# Bluetooth.net
KiCad netlist of a schematic drawn in Altium Designer
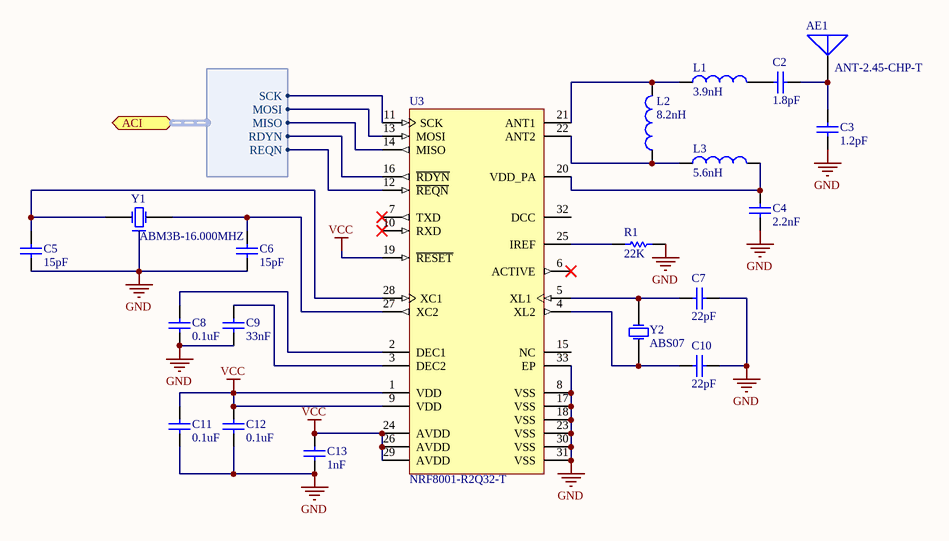
[diagram p0: Bluetooth.SchDoc]

(export (version "E")
  (design (tool "Eeschema 10.0.6"))
  (components
    (comp (ref "AE1")
      (value "ANT-2.45-CHP-T")
      (footprint "ANT-2.45-CHP")
      (fields (field (name "MANUFACTURER") "Taiyo Yuden"))
      (libsource (lib "Components") (part "ANT-2.45-CHP-T"))
    )
    (comp (ref "C2")
      (value "1.8pF")
      (footprint "C0402[1005X55]")
      (description "1.8pF 50V 0.05pF 0402 (1005 Metric)")
      (fields (field (name "PARTNUMBER") "GRM1555C1H1R8WA01D") (field (name "MANUFACTURER") "Murata"))
      (libsource (lib "Capacitors") (part "CAP_1.8pF_50V_0402_0.05pF"))
    )
    (comp (ref "C3")
      (value "1.2pF")
      (footprint "C0402[1005X55]")
      (description "1.2pF 50V 0.05pF 0402 (1005 Metric)")
      (fields (field (name "PARTNUMBER") "GRM1555C1H1R2WA01D") (field (name "MANUFACTURER") "Murata"))
      (libsource (lib "Capacitors") (part "CAP_1.2pF_50V_0402_0.05pF"))
    )
    (comp (ref "C4")
      (value "2.2nF")
      (footprint "C0402[1005X55]")
      (description "2.2nF 50V 10% 0402 (1005 Metric)")
      (fields (field (name "PARTNUMBER") "GCM155R71H222KA37D") (field (name "MANUFACTURER") "Murata"))
      (libsource (lib "Capacitors") (part "CAP_2.2nF_50V_0402_10%"))
    )
    (comp (ref "C5")
      (value "15pF")
      (footprint "C0402[1005X55]")
      (description "15pF 50V 5% 0402 (1005 Metric)")
      (fields (field (name "PARTNUMBER") "GRM1555C1H150JA01D") (field (name "MANUFACTURER") "Murata"))
      (libsource (lib "Capacitors") (part "CAP_15pF_50V_0402_5%"))
    )
    (comp (ref "C6")
      (value "15pF")
      (footprint "C0402[1005X55]")
      (description "15pF 50V 5% 0402 (1005 Metric)")
      (fields (field (name "PARTNUMBER") "GRM1555C1H150JA01D") (field (name "MANUFACTURER") "Murata"))
      (libsource (lib "Capacitors") (part "CAP_15pF_50V_0402_5%"))
    )
    (comp (ref "C7")
      (value "22pF")
      (footprint "C0402[1005X55]")
      (description "22pF 50V 1% 0402 (1005 Metric)")
      (fields (field (name "PARTNUMBER") "GRM1555C1H220FA01D") (field (name "MANUFACTURER") "Murata"))
      (libsource (lib "Capacitors") (part "CAP_22pF_50V_0402_1%"))
    )
    (comp (ref "C8")
      (value "0.1uF")
      (footprint "C0402[1005X55]")
      (description "0.1uF 6.3V 10% 0402 (1005 Metric)")
      (fields (field (name "PARTNUMBER") "GRM155R70J104KA01D") (field (name "MANUFACTURER") "Murata"))
      (libsource (lib "Capacitors") (part "CAP_0.1uF_6.3V_0402_10%"))
    )
    (comp (ref "C9")
      (value "33nF")
      (footprint "C0402[1005X55]")
      (description "33nF 50V 10% 0402 (1005 Metric)")
      (fields (field (name "PARTNUMBER") "GRM155R71H333KE14D") (field (name "MANUFACTURER") "Murata"))
      (libsource (lib "Capacitors") (part "CAP_33nF_50V_0402_10%"))
    )
    (comp (ref "C10")
      (value "22pF")
      (footprint "C0402[1005X55]")
      (description "22pF 50V 1% 0402 (1005 Metric)")
      (fields (field (name "PARTNUMBER") "GRM1555C1H220FA01D") (field (name "MANUFACTURER") "Murata"))
      (libsource (lib "Capacitors") (part "CAP_22pF_50V_0402_1%"))
    )
    (comp (ref "C11")
      (value "0.1uF")
      (footprint "C0402[1005X55]")
      (description "0.1uF 6.3V 10% 0402 (1005 Metric)")
      (fields (field (name "PARTNUMBER") "GRM155R70J104KA01D") (field (name "MANUFACTURER") "Murata"))
      (libsource (lib "Capacitors") (part "CAP_0.1uF_6.3V_0402_10%"))
    )
    (comp (ref "C12")
      (value "0.1uF")
      (footprint "C0402[1005X55]")
      (description "0.1uF 6.3V 10% 0402 (1005 Metric)")
      (fields (field (name "PARTNUMBER") "GRM155R70J104KA01D") (field (name "MANUFACTURER") "Murata"))
      (libsource (lib "Capacitors") (part "CAP_0.1uF_6.3V_0402_10%"))
    )
    (comp (ref "C13")
      (value "1nF")
      (footprint "C0402[1005X55]")
      (description "1nF 50V 5% 0402 (1005 Metric)")
      (fields (field (name "PARTNUMBER") "GRM1555C1H102JA01D") (field (name "MANUFACTURER") "Murata"))
      (libsource (lib "Capacitors") (part "CAP_1nF_50V_0402_5%"))
    )
    (comp (ref "L1")
      (value "3.9nH")
      (footprint "IND0402")
      (description "3.9nH +/-0.3nH 0.3A 0402")
      (fields (field (name "PARTNUMBER") "LQG15HS3N9S02D") (field (name "MANUFACTURER") "Murata"))
      (libsource (lib "Inductors") (part "IND_3.9nH_0.3A_0402_0.3nH"))
    )
    (comp (ref "L2")
      (value "8.2nH")
      (footprint "IND0402")
      (description "8.2nH 5% 0.3A 0402")
      (fields (field (name "PARTNUMBER") "LQG15HS8N2J02D") (field (name "MANUFACTURER") "Murata"))
      (libsource (lib "Inductors") (part "IND_8.2nH_0.3A_0402_5%"))
    )
    (comp (ref "L3")
      (value "5.6nH")
      (footprint "IND0402")
      (description "5.6nH +/-0.3nH 0.3A 0402")
      (fields (field (name "PARTNUMBER") "LQG15HS5N6S02D") (field (name "MANUFACTURER") "Murata"))
      (libsource (lib "Inductors") (part "IND_5.6nH_0.3A_0402_0.3nH"))
    )
    (comp (ref "R1")
      (value "22K")
      (footprint "R0402[1005]")
      (description "22K 0.063W 1% 0402 (1005 Metric)")
      (fields (field (name "MANUFACTURER") "KOA Speer") (field (name "PARTNUMBER") "RK73H1ETTP2202F"))
      (libsource (lib "Resistors") (part "RES_22K_0402_1%"))
    )
    (comp (ref "U3")
      (value "NRF8001-R2Q32-T")
      (footprint "NRSC-QFN-32_M")
      (description "Single-Chip Bluetooth(R) Low Energy Solution, 1.9 to 3.6 V, -40 to 85 degC, 32-Pin QFN, RoHS, Tray")
      (fields (field (name "TOLERANCE") "20%"))
      (libsource (lib "Altium Content Vault") (part "NRSC-NRF8001-R2Q32-T-32"))
    )
    (comp (ref "Y1")
      (value "ABM3B-16.000MHZ")
      (footprint "ABRA-ABM3B-4_V")
      (fields (field (name "PARTNUMBER") "ABM3B-16.000MHZ-10-1-U-T") (field (name "MANUFACTURER") "ABRACON"))
      (libsource (lib "Components") (part "ABM3B-16.000MHZ-10-1-U-T"))
    )
    (comp (ref "Y2")
      (value "ABS07")
      (footprint "ABS07")
      (fields (field (name "MANUFACTURER") "Abracon") (field (name "PARTNUMBER") "ABS07-32.768KHZ-T"))
      (libsource (lib "Components") (part "ABS07"))
    )
  )
  (nets
    (net (code "2") (name "/MISO") (class "Default")
      (node (ref "U3") (pin "14") (pinfunction "MISO_14") (pintype "output"))
    )
    (net (code "3") (name "/MOSI") (class "Default")
      (node (ref "U3") (pin "13") (pinfunction "MOSI_13") (pintype "input"))
    )
    (net (code "4") (name "/RDYN") (class "Default")
      (node (ref "U3") (pin "16") (pinfunction "~{RDYN}_16") (pintype "output"))
    )
    (net (code "5") (name "/REQN") (class "Default")
      (node (ref "U3") (pin "12") (pinfunction "~{REQN}_12") (pintype "input"))
    )
    (net (code "6") (name "/SCK") (class "Default")
      (node (ref "U3") (pin "11") (pinfunction "SCK_11") (pintype "input"))
    )
    (net (code "8") (name "GND") (class "Default")
      (node (ref "C10") (pin "2") (pinfunction "2_2") (pintype "passive"))
      (node (ref "C11") (pin "1") (pinfunction "1_1") (pintype "passive"))
      (node (ref "C12") (pin "1") (pinfunction "1_1") (pintype "passive"))
      (node (ref "C13") (pin "1") (pinfunction "1_1") (pintype "passive"))
      (node (ref "C3") (pin "1") (pinfunction "1_1") (pintype "passive"))
      (node (ref "C4") (pin "1") (pinfunction "1_1") (pintype "passive"))
      (node (ref "C5") (pin "1") (pinfunction "1_1") (pintype "passive"))
      (node (ref "C6") (pin "1") (pinfunction "1_1") (pintype "passive"))
      (node (ref "C7") (pin "2") (pinfunction "2_2") (pintype "passive"))
      (node (ref "C8") (pin "1") (pinfunction "1_1") (pintype "passive"))
      (node (ref "C9") (pin "1") (pinfunction "1_1") (pintype "passive"))
      (node (ref "R1") (pin "1") (pinfunction "1_1") (pintype "passive"))
      (node (ref "U3") (pin "17") (pinfunction "VSS_17") (pintype "power_in"))
      (node (ref "U3") (pin "18") (pinfunction "VSS_18") (pintype "power_in"))
      (node (ref "U3") (pin "23") (pinfunction "VSS_23") (pintype "power_in"))
      (node (ref "U3") (pin "30") (pinfunction "VSS_30") (pintype "power_in"))
      (node (ref "U3") (pin "31") (pinfunction "VSS_31") (pintype "power_in"))
      (node (ref "U3") (pin "33") (pinfunction "EP_33") (pintype "power_in"))
      (node (ref "U3") (pin "8") (pinfunction "VSS_8") (pintype "power_in"))
      (node (ref "Y1") (pin "2") (pinfunction "2_2") (pintype "passive"))
    )
    (net (code "9") (name "Net-(AE1-Pad1)") (class "Default")
      (node (ref "AE1") (pin "1") (pinfunction "1_1") (pintype "passive"))
      (node (ref "C2") (pin "2") (pinfunction "2_2") (pintype "passive"))
      (node (ref "C3") (pin "2") (pinfunction "2_2") (pintype "passive"))
    )
    (net (code "10") (name "Net-(C2-Pad1)") (class "Default")
      (node (ref "C2") (pin "1") (pinfunction "1_1") (pintype "passive"))
      (node (ref "L1") (pin "2") (pinfunction "2_2") (pintype "passive"))
    )
    (net (code "11") (name "Net-(U3-ANT1)") (class "Default")
      (node (ref "L1") (pin "1") (pinfunction "1_1") (pintype "passive"))
      (node (ref "L2") (pin "2") (pinfunction "2_2") (pintype "passive"))
      (node (ref "U3") (pin "21") (pinfunction "ANT1_21") (pintype "passive"))
    )
    (net (code "12") (name "Net-(U3-ANT2)") (class "Default")
      (node (ref "L2") (pin "1") (pinfunction "1_1") (pintype "passive"))
      (node (ref "L3") (pin "1") (pinfunction "1_1") (pintype "passive"))
      (node (ref "U3") (pin "22") (pinfunction "ANT2_22") (pintype "passive"))
    )
    (net (code "13") (name "Net-(U3-DEC1)") (class "Default")
      (node (ref "C8") (pin "2") (pinfunction "2_2") (pintype "passive"))
      (node (ref "U3") (pin "2") (pinfunction "DEC1_2") (pintype "power_in"))
    )
    (net (code "14") (name "Net-(U3-DEC2)") (class "Default")
      (node (ref "C9") (pin "2") (pinfunction "2_2") (pintype "passive"))
      (node (ref "U3") (pin "3") (pinfunction "DEC2_3") (pintype "power_in"))
    )
    (net (code "15") (name "Net-(U3-IREF)") (class "Default")
      (node (ref "R1") (pin "2") (pinfunction "2_2") (pintype "passive"))
      (node (ref "U3") (pin "25") (pinfunction "IREF_25") (pintype "passive"))
    )
    (net (code "16") (name "Net-(U3-VDD_PA)") (class "Default")
      (node (ref "C4") (pin "2") (pinfunction "2_2") (pintype "passive"))
      (node (ref "L3") (pin "2") (pinfunction "2_2") (pintype "passive"))
      (node (ref "U3") (pin "20") (pinfunction "VDD_PA_20") (pintype "power_in"))
    )
    (net (code "17") (name "Net-(U3-XC1)") (class "Default")
      (node (ref "C5") (pin "2") (pinfunction "2_2") (pintype "passive"))
      (node (ref "U3") (pin "28") (pinfunction "XC1_28") (pintype "input"))
      (node (ref "Y1") (pin "1") (pinfunction "X1_1") (pintype "passive"))
    )
    (net (code "18") (name "Net-(U3-XC2)") (class "Default")
      (node (ref "C6") (pin "2") (pinfunction "2_2") (pintype "passive"))
      (node (ref "U3") (pin "27") (pinfunction "XC2_27") (pintype "output"))
      (node (ref "Y1") (pin "3") (pinfunction "X2_3") (pintype "passive"))
    )
    (net (code "19") (name "Net-(U3-XL1)") (class "Default")
      (node (ref "C7") (pin "1") (pinfunction "1_1") (pintype "passive"))
      (node (ref "U3") (pin "5") (pinfunction "XL1_5") (pintype "input"))
      (node (ref "Y2") (pin "2") (pinfunction "X2_2") (pintype "passive"))
    )
    (net (code "20") (name "Net-(U3-XL2)") (class "Default")
      (node (ref "C10") (pin "1") (pinfunction "1_1") (pintype "passive"))
      (node (ref "U3") (pin "4") (pinfunction "XL2_4") (pintype "output"))
      (node (ref "Y2") (pin "1") (pinfunction "X1_1") (pintype "passive"))
    )
    (net (code "21") (name "VCC") (class "Default")
      (node (ref "C11") (pin "2") (pinfunction "2_2") (pintype "passive"))
      (node (ref "C12") (pin "2") (pinfunction "2_2") (pintype "passive"))
      (node (ref "C13") (pin "2") (pinfunction "2_2") (pintype "passive"))
      (node (ref "U3") (pin "1") (pinfunction "VDD_1") (pintype "power_in"))
      (node (ref "U3") (pin "19") (pinfunction "~{RESET}_19") (pintype "input"))
      (node (ref "U3") (pin "24") (pinfunction "AVDD_24") (pintype "power_in"))
      (node (ref "U3") (pin "26") (pinfunction "AVDD_26") (pintype "power_in"))
      (node (ref "U3") (pin "29") (pinfunction "AVDD_29") (pintype "power_in"))
      (node (ref "U3") (pin "9") (pinfunction "VDD_9") (pintype "power_in"))
    )
    (net (code "22") (name "unconnected-(U3-ACTIVE-Pad6)") (class "Default")
      (node (ref "U3") (pin "6") (pinfunction "ACTIVE_6") (pintype "output+no_connect"))
    )
    (net (code "23") (name "unconnected-(U3-DCC-Pad32)") (class "Default")
      (node (ref "U3") (pin "32") (pinfunction "DCC_32") (pintype "power_in"))
    )
    (net (code "24") (name "unconnected-(U3-NC-Pad15)") (class "Default")
      (node (ref "U3") (pin "15") (pinfunction "NC_15") (pintype "passive"))
    )
    (net (code "25") (name "unconnected-(U3-RXD-Pad10)") (class "Default")
      (node (ref "U3") (pin "10") (pinfunction "RXD_10") (pintype "input+no_connect"))
    )
    (net (code "26") (name "unconnected-(U3-TXD-Pad7)") (class "Default")
      (node (ref "U3") (pin "7") (pinfunction "TXD_7") (pintype "output+no_connect"))
    )
  )
)
